# pcb_pf.net
KiCad netlist of a schematic drawn in EAGLE
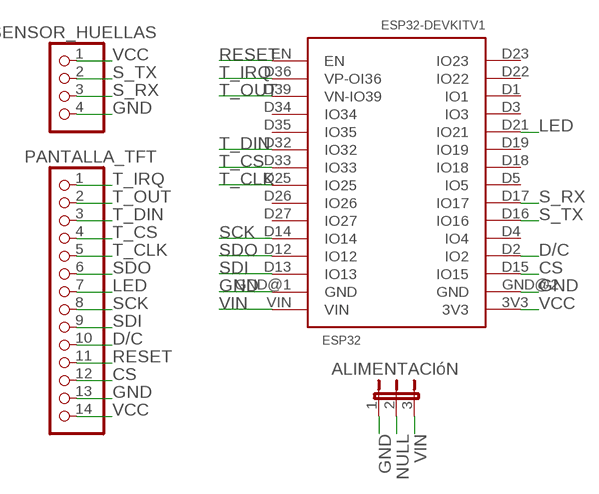
[diagram p0: schematic, sheet 1]

(export (version "E")
  (design (tool "Eeschema 10.0.6"))
  (components
    (comp (ref "ALIMENTACIóN")
      (value "JP2E")
      (footprint "eagle-import:JP2")
      (libsource (lib "eagle-import") (part "JP2E"))
    )
    (comp (ref "ESP32")
      (value "ESP32DEVKITV1")
      (footprint "eagle-import:ESP32-DEVKITV1")
      (libsource (lib "eagle-import") (part "ESP32DEVKITV1"))
    )
    (comp (ref "PANTALLA_TFT")
      (value "PINHD-1X14")
      (footprint "eagle-import:1X14")
      (libsource (lib "eagle-import") (part "PINHD-1X14"))
    )
    (comp (ref "SENSOR_HUELLAS")
      (value "PINHD-1X4")
      (footprint "eagle-import:1X04")
      (libsource (lib "eagle-import") (part "PINHD-1X4"))
    )
  )
  (nets
    (net (code "1") (name "/CS") (class "Default")
      (node (ref "ESP32") (pin "D15") (pinfunction "IO15_D15") (pintype "bidirectional"))
      (node (ref "PANTALLA_TFT") (pin "12") (pinfunction "12_12") (pintype "passive"))
    )
    (net (code "2") (name "/D{slash}C") (class "Default")
      (node (ref "ESP32") (pin "D2") (pinfunction "IO2_D2") (pintype "bidirectional"))
      (node (ref "PANTALLA_TFT") (pin "10") (pinfunction "10_10") (pintype "passive"))
    )
    (net (code "3") (name "/GND") (class "Default")
      (node (ref "ALIMENTACIóN") (pin "1") (pinfunction "1_1") (pintype "passive"))
      (node (ref "ESP32") (pin "GND@1") (pinfunction "GND_GND@1") (pintype "bidirectional"))
      (node (ref "ESP32") (pin "GND@2") (pinfunction "GND_GND@2") (pintype "bidirectional"))
      (node (ref "PANTALLA_TFT") (pin "13") (pinfunction "13_13") (pintype "passive"))
      (node (ref "SENSOR_HUELLAS") (pin "4") (pinfunction "4_4") (pintype "passive"))
    )
    (net (code "4") (name "/LED") (class "Default")
      (node (ref "ESP32") (pin "D21") (pinfunction "IO21_D21") (pintype "bidirectional"))
      (node (ref "PANTALLA_TFT") (pin "7") (pinfunction "7_7") (pintype "passive"))
    )
    (net (code "5") (name "/NULL") (class "Default")
      (node (ref "ALIMENTACIóN") (pin "2") (pinfunction "2_2") (pintype "passive"))
    )
    (net (code "6") (name "/RESET") (class "Default")
      (node (ref "ESP32") (pin "EN") (pinfunction "EN_EN") (pintype "bidirectional"))
      (node (ref "PANTALLA_TFT") (pin "11") (pinfunction "11_11") (pintype "passive"))
    )
    (net (code "7") (name "/SCK") (class "Default")
      (node (ref "ESP32") (pin "D14") (pinfunction "IO14_D14") (pintype "bidirectional"))
      (node (ref "PANTALLA_TFT") (pin "8") (pinfunction "8_8") (pintype "passive"))
    )
    (net (code "8") (name "/SDI") (class "Default")
      (node (ref "ESP32") (pin "D13") (pinfunction "IO13_D13") (pintype "bidirectional"))
      (node (ref "PANTALLA_TFT") (pin "9") (pinfunction "9_9") (pintype "passive"))
    )
    (net (code "9") (name "/SDO") (class "Default")
      (node (ref "ESP32") (pin "D12") (pinfunction "IO12_D12") (pintype "bidirectional"))
      (node (ref "PANTALLA_TFT") (pin "6") (pinfunction "6_6") (pintype "passive"))
    )
    (net (code "10") (name "/S_RX") (class "Default")
      (node (ref "ESP32") (pin "D17") (pinfunction "IO17_D17") (pintype "bidirectional"))
      (node (ref "SENSOR_HUELLAS") (pin "3") (pinfunction "3_3") (pintype "passive"))
    )
    (net (code "11") (name "/S_TX") (class "Default")
      (node (ref "ESP32") (pin "D16") (pinfunction "IO16_D16") (pintype "bidirectional"))
      (node (ref "SENSOR_HUELLAS") (pin "2") (pinfunction "2_2") (pintype "passive"))
    )
    (net (code "12") (name "/T_CLK") (class "Default")
      (node (ref "ESP32") (pin "D25") (pinfunction "IO25_D25") (pintype "bidirectional"))
      (node (ref "PANTALLA_TFT") (pin "5") (pinfunction "5_5") (pintype "passive"))
    )
    (net (code "13") (name "/T_CS") (class "Default")
      (node (ref "ESP32") (pin "D33") (pinfunction "IO33_D33") (pintype "bidirectional"))
      (node (ref "PANTALLA_TFT") (pin "4") (pinfunction "4_4") (pintype "passive"))
    )
    (net (code "14") (name "/T_DIN") (class "Default")
      (node (ref "ESP32") (pin "D32") (pinfunction "IO32_D32") (pintype "bidirectional"))
      (node (ref "PANTALLA_TFT") (pin "3") (pinfunction "3_3") (pintype "passive"))
    )
    (net (code "15") (name "/T_IRQ") (class "Default")
      (node (ref "ESP32") (pin "D36") (pinfunction "VP-OI36_D36") (pintype "bidirectional"))
      (node (ref "PANTALLA_TFT") (pin "1") (pinfunction "1_1") (pintype "passive"))
    )
    (net (code "16") (name "/T_OUT") (class "Default")
      (node (ref "ESP32") (pin "D39") (pinfunction "VN-IO39_D39") (pintype "bidirectional"))
      (node (ref "PANTALLA_TFT") (pin "2") (pinfunction "2_2") (pintype "passive"))
    )
    (net (code "17") (name "/VCC") (class "Default")
      (node (ref "ESP32") (pin "3V3") (pinfunction "3V3_3V3") (pintype "bidirectional"))
      (node (ref "PANTALLA_TFT") (pin "14") (pinfunction "14_14") (pintype "passive"))
      (node (ref "SENSOR_HUELLAS") (pin "1") (pinfunction "1_1") (pintype "passive"))
    )
    (net (code "18") (name "/VIN") (class "Default")
      (node (ref "ALIMENTACIóN") (pin "3") (pinfunction "3_3") (pintype "passive"))
      (node (ref "ESP32") (pin "VIN") (pinfunction "VIN_VIN") (pintype "bidirectional"))
    )
    (net (code "19") (name "unconnected-(ESP32-IO1-PadD1)") (class "Default")
      (node (ref "ESP32") (pin "D1") (pinfunction "IO1_D1") (pintype "bidirectional"))
    )
    (net (code "20") (name "unconnected-(ESP32-IO3-PadD3)") (class "Default")
      (node (ref "ESP32") (pin "D3") (pinfunction "IO3_D3") (pintype "bidirectional"))
    )
    (net (code "21") (name "unconnected-(ESP32-IO4-PadD4)") (class "Default")
      (node (ref "ESP32") (pin "D4") (pinfunction "IO4_D4") (pintype "bidirectional"))
    )
    (net (code "22") (name "unconnected-(ESP32-IO5-PadD5)") (class "Default")
      (node (ref "ESP32") (pin "D5") (pinfunction "IO5_D5") (pintype "bidirectional"))
    )
    (net (code "23") (name "unconnected-(ESP32-IO18-PadD18)") (class "Default")
      (node (ref "ESP32") (pin "D18") (pinfunction "IO18_D18") (pintype "bidirectional"))
    )
    (net (code "24") (name "unconnected-(ESP32-IO19-PadD19)") (class "Default")
      (node (ref "ESP32") (pin "D19") (pinfunction "IO19_D19") (pintype "bidirectional"))
    )
    (net (code "25") (name "unconnected-(ESP32-IO22-PadD22)") (class "Default")
      (node (ref "ESP32") (pin "D22") (pinfunction "IO22_D22") (pintype "bidirectional"))
    )
    (net (code "26") (name "unconnected-(ESP32-IO23-PadD23)") (class "Default")
      (node (ref "ESP32") (pin "D23") (pinfunction "IO23_D23") (pintype "bidirectional"))
    )
    (net (code "27") (name "unconnected-(ESP32-IO26-PadD26)") (class "Default")
      (node (ref "ESP32") (pin "D26") (pinfunction "IO26_D26") (pintype "bidirectional"))
    )
    (net (code "28") (name "unconnected-(ESP32-IO27-PadD27)") (class "Default")
      (node (ref "ESP32") (pin "D27") (pinfunction "IO27_D27") (pintype "bidirectional"))
    )
    (net (code "29") (name "unconnected-(ESP32-IO34-PadD34)") (class "Default")
      (node (ref "ESP32") (pin "D34") (pinfunction "IO34_D34") (pintype "bidirectional"))
    )
    (net (code "30") (name "unconnected-(ESP32-IO35-PadD35)") (class "Default")
      (node (ref "ESP32") (pin "D35") (pinfunction "IO35_D35") (pintype "bidirectional"))
    )
  )
)
